# 9xVoice_MikeB_TH_v101.net
KiCad netlist of a schematic drawn in EAGLE
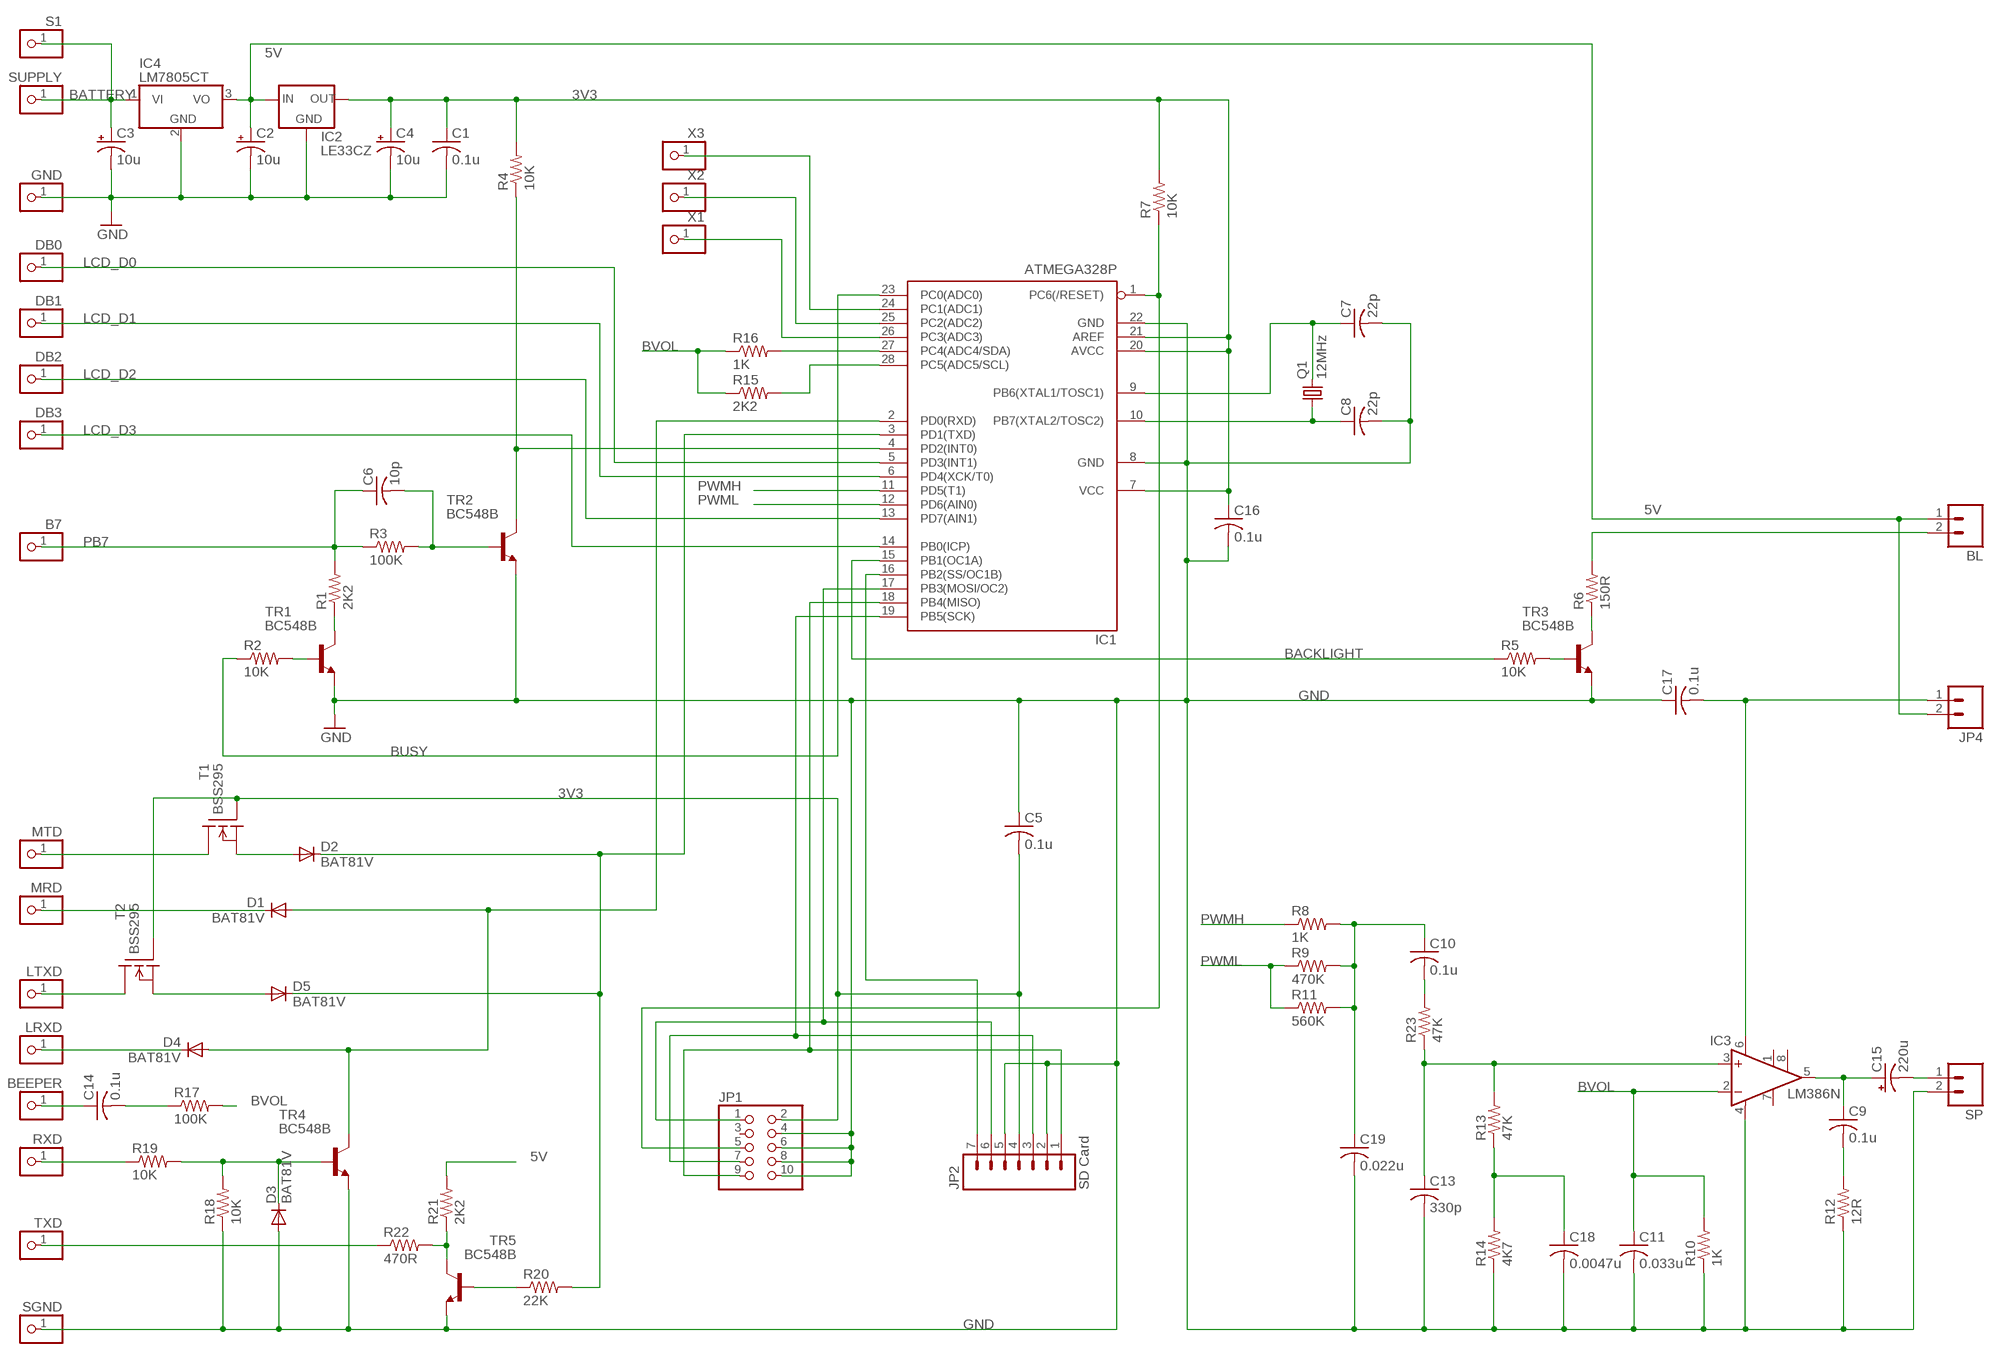
[diagram p0: schematic, sheet 1]

(export (version "E")
  (design (tool "Eeschema 10.0.6"))
  (components
    (comp (ref "B7")
      (value "PINHD-1X1")
      (footprint "eagle-import:1X01")
      (libsource (lib "eagle-import") (part "PINHD-1X1"))
    )
    (comp (ref "BEEPER")
      (value "PINHD-1X1")
      (footprint "eagle-import:1X01")
      (libsource (lib "eagle-import") (part "PINHD-1X1"))
    )
    (comp (ref "BL")
      (value "M02PTH")
      (footprint "eagle-import:1X02")
      (libsource (lib "eagle-import") (part "M02PTH"))
    )
    (comp (ref "C1")
      (value "0.1u")
      (footprint "eagle-import:C025-024X044")
      (libsource (lib "eagle-import") (part "C-US025-024X044"))
    )
    (comp (ref "C2")
      (value "10u")
      (footprint "eagle-import:E1,8-4")
      (libsource (lib "eagle-import") (part "CPOL-USE1.8-4"))
    )
    (comp (ref "C3")
      (value "10u")
      (footprint "eagle-import:E1,8-4")
      (libsource (lib "eagle-import") (part "CPOL-USE1.8-4"))
    )
    (comp (ref "C4")
      (value "10u")
      (footprint "eagle-import:E1,8-4")
      (libsource (lib "eagle-import") (part "CPOL-USE1.8-4"))
    )
    (comp (ref "C5")
      (value "0.1u")
      (footprint "eagle-import:C025-024X044")
      (libsource (lib "eagle-import") (part "C-US025-024X044"))
    )
    (comp (ref "C6")
      (value "10p")
      (footprint "eagle-import:C025-024X044")
      (libsource (lib "eagle-import") (part "C-US025-024X044"))
    )
    (comp (ref "C7")
      (value "22p")
      (footprint "eagle-import:C025-024X044")
      (libsource (lib "eagle-import") (part "C-US025-024X044"))
    )
    (comp (ref "C8")
      (value "22p")
      (footprint "eagle-import:C025-024X044")
      (libsource (lib "eagle-import") (part "C-US025-024X044"))
    )
    (comp (ref "C9")
      (value "0.1u")
      (footprint "eagle-import:C025-024X044")
      (libsource (lib "eagle-import") (part "C-US025-024X044"))
    )
    (comp (ref "C10")
      (value "0.1u")
      (footprint "eagle-import:C025-024X044")
      (libsource (lib "eagle-import") (part "C-US025-024X044"))
    )
    (comp (ref "C11")
      (value "0.033u")
      (footprint "eagle-import:C025-024X044")
      (libsource (lib "eagle-import") (part "C-US025-024X044"))
    )
    (comp (ref "C13")
      (value "330p")
      (footprint "eagle-import:C025-024X044")
      (libsource (lib "eagle-import") (part "C-US025-024X044"))
    )
    (comp (ref "C14")
      (value "0.1u")
      (footprint "eagle-import:C025-024X044")
      (libsource (lib "eagle-import") (part "C-US025-024X044"))
    )
    (comp (ref "C15")
      (value "220u")
      (footprint "eagle-import:E2,5-6")
      (libsource (lib "eagle-import") (part "CPOL-USE2.5-6"))
    )
    (comp (ref "C16")
      (value "0.1u")
      (footprint "eagle-import:C025-024X044")
      (libsource (lib "eagle-import") (part "C-US025-024X044"))
    )
    (comp (ref "C17")
      (value "0.1u")
      (footprint "eagle-import:C025-024X044")
      (libsource (lib "eagle-import") (part "C-US025-024X044"))
    )
    (comp (ref "C18")
      (value "0.0047u")
      (footprint "eagle-import:C025-024X044")
      (libsource (lib "eagle-import") (part "C-US025-024X044"))
    )
    (comp (ref "C19")
      (value "0.022u")
      (footprint "eagle-import:C025-024X044")
      (libsource (lib "eagle-import") (part "C-US025-024X044"))
    )
    (comp (ref "D1")
      (value "BAT81V")
      (footprint "eagle-import:D-2.5")
      (libsource (lib "eagle-import") (part "DIODE-D-2.5"))
    )
    (comp (ref "D2")
      (value "BAT81V")
      (footprint "eagle-import:D-2.5")
      (libsource (lib "eagle-import") (part "DIODE-D-2.5"))
    )
    (comp (ref "D3")
      (value "BAT81V")
      (footprint "eagle-import:D-2.5")
      (libsource (lib "eagle-import") (part "DIODE-D-2.5"))
    )
    (comp (ref "D4")
      (value "BAT81V")
      (footprint "eagle-import:D-2.5")
      (libsource (lib "eagle-import") (part "DIODE-D-2.5"))
    )
    (comp (ref "D5")
      (value "BAT81V")
      (footprint "eagle-import:D-2.5")
      (libsource (lib "eagle-import") (part "DIODE-D-2.5"))
    )
    (comp (ref "DB0")
      (value "PINHD-1X1")
      (footprint "eagle-import:1X01")
      (libsource (lib "eagle-import") (part "PINHD-1X1"))
    )
    (comp (ref "DB1")
      (value "PINHD-1X1")
      (footprint "eagle-import:1X01")
      (libsource (lib "eagle-import") (part "PINHD-1X1"))
    )
    (comp (ref "DB2")
      (value "PINHD-1X1")
      (footprint "eagle-import:1X01")
      (libsource (lib "eagle-import") (part "PINHD-1X1"))
    )
    (comp (ref "DB3")
      (value "PINHD-1X1")
      (footprint "eagle-import:1X01")
      (libsource (lib "eagle-import") (part "PINHD-1X1"))
    )
    (comp (ref "GND")
      (value "PINHD-1X1")
      (footprint "eagle-import:1X01")
      (libsource (lib "eagle-import") (part "PINHD-1X1"))
    )
    (comp (ref "IC1")
      (value "ATMEGA328P")
      (footprint "eagle-import:DIL28-3")
      (libsource (lib "eagle-import") (part "MEGA8-P"))
    )
    (comp (ref "IC2")
      (value "LE33CZ")
      (footprint "eagle-import:78LXX")
      (libsource (lib "eagle-import") (part "78LXX"))
    )
    (comp (ref "IC3")
      (value "LM386N")
      (footprint "eagle-import:DIL08")
      (libsource (lib "eagle-import") (part "LM386?-N1"))
    )
    (comp (ref "IC4")
      (value "LM7805CT")
      (footprint "eagle-import:TO220H")
      (libsource (lib "eagle-import") (part "78T05"))
    )
    (comp (ref "JP1")
      (value "PINHD-2X5")
      (footprint "eagle-import:2X05")
      (libsource (lib "eagle-import") (part "PINHD-2X5"))
    )
    (comp (ref "JP2")
      (value "SD Card")
      (footprint "eagle-import:1X07")
      (libsource (lib "eagle-import") (part "M07"))
    )
    (comp (ref "JP4")
      (value "M02PTH")
      (footprint "eagle-import:1X02")
      (libsource (lib "eagle-import") (part "M02PTH"))
    )
    (comp (ref "LRXD")
      (value "PINHD-1X1")
      (footprint "eagle-import:1X01")
      (libsource (lib "eagle-import") (part "PINHD-1X1"))
    )
    (comp (ref "LTXD")
      (value "PINHD-1X1")
      (footprint "eagle-import:1X01")
      (libsource (lib "eagle-import") (part "PINHD-1X1"))
    )
    (comp (ref "MRD")
      (value "PINHD-1X1")
      (footprint "eagle-import:1X01")
      (libsource (lib "eagle-import") (part "PINHD-1X1"))
    )
    (comp (ref "MTD")
      (value "PINHD-1X1")
      (footprint "eagle-import:1X01")
      (libsource (lib "eagle-import") (part "PINHD-1X1"))
    )
    (comp (ref "Q1")
      (value "12MHz")
      (footprint "eagle-import:HC49US")
      (libsource (lib "eagle-import") (part "CRYSTALHC49US"))
    )
    (comp (ref "R1")
      (value "2K2")
      (footprint "eagle-import:0207_2V")
      (libsource (lib "eagle-import") (part "R-US_0207/2V"))
    )
    (comp (ref "R2")
      (value "10K")
      (footprint "eagle-import:0207_10")
      (libsource (lib "eagle-import") (part "R-US_0207/10"))
    )
    (comp (ref "R3")
      (value "100K")
      (footprint "eagle-import:0207_2V")
      (libsource (lib "eagle-import") (part "R-US_0207/2V"))
    )
    (comp (ref "R4")
      (value "10K")
      (footprint "eagle-import:0207_2V")
      (libsource (lib "eagle-import") (part "R-US_0207/2V"))
    )
    (comp (ref "R5")
      (value "10K")
      (footprint "eagle-import:0207_2V")
      (libsource (lib "eagle-import") (part "R-US_0207/2V"))
    )
    (comp (ref "R6")
      (value "150R")
      (footprint "eagle-import:0207_2V")
      (libsource (lib "eagle-import") (part "R-US_0207/2V"))
    )
    (comp (ref "R7")
      (value "10K")
      (footprint "eagle-import:0207_2V")
      (libsource (lib "eagle-import") (part "R-US_0207/2V"))
    )
    (comp (ref "R8")
      (value "1K")
      (footprint "eagle-import:0207_2V")
      (libsource (lib "eagle-import") (part "R-US_0207/2V"))
    )
    (comp (ref "R9")
      (value "470K")
      (footprint "eagle-import:0207_2V")
      (libsource (lib "eagle-import") (part "R-US_0207/2V"))
    )
    (comp (ref "R10")
      (value "1K")
      (footprint "eagle-import:0207_2V")
      (libsource (lib "eagle-import") (part "R-US_0207/2V"))
    )
    (comp (ref "R11")
      (value "560K")
      (footprint "eagle-import:0207_2V")
      (libsource (lib "eagle-import") (part "R-US_0207/2V"))
    )
    (comp (ref "R12")
      (value "12R")
      (footprint "eagle-import:0207_2V")
      (libsource (lib "eagle-import") (part "R-US_0207/2V"))
    )
    (comp (ref "R13")
      (value "47K")
      (footprint "eagle-import:0207_2V")
      (libsource (lib "eagle-import") (part "R-US_0207/2V"))
    )
    (comp (ref "R14")
      (value "4K7")
      (footprint "eagle-import:0207_2V")
      (libsource (lib "eagle-import") (part "R-US_0207/2V"))
    )
    (comp (ref "R15")
      (value "2K2")
      (footprint "eagle-import:0207_2V")
      (libsource (lib "eagle-import") (part "R-US_0207/2V"))
    )
    (comp (ref "R16")
      (value "1K")
      (footprint "eagle-import:0207_2V")
      (libsource (lib "eagle-import") (part "R-US_0207/2V"))
    )
    (comp (ref "R17")
      (value "100K")
      (footprint "eagle-import:0207_2V")
      (libsource (lib "eagle-import") (part "R-US_0207/2V"))
    )
    (comp (ref "R18")
      (value "10K")
      (footprint "eagle-import:0207_2V")
      (libsource (lib "eagle-import") (part "R-US_0207/2V"))
    )
    (comp (ref "R19")
      (value "10K")
      (footprint "eagle-import:0207_2V")
      (libsource (lib "eagle-import") (part "R-US_0207/2V"))
    )
    (comp (ref "R20")
      (value "22K")
      (footprint "eagle-import:0207_2V")
      (libsource (lib "eagle-import") (part "R-US_0207/2V"))
    )
    (comp (ref "R21")
      (value "2K2")
      (footprint "eagle-import:0207_2V")
      (libsource (lib "eagle-import") (part "R-US_0207/2V"))
    )
    (comp (ref "R22")
      (value "470R")
      (footprint "eagle-import:0207_2V")
      (libsource (lib "eagle-import") (part "R-US_0207/2V"))
    )
    (comp (ref "R23")
      (value "47K")
      (footprint "eagle-import:0207_2V")
      (libsource (lib "eagle-import") (part "R-US_0207/2V"))
    )
    (comp (ref "RXD")
      (value "PINHD-1X1")
      (footprint "eagle-import:1X01")
      (libsource (lib "eagle-import") (part "PINHD-1X1"))
    )
    (comp (ref "S1")
      (value "PINHD-1X1")
      (footprint "eagle-import:1X01")
      (libsource (lib "eagle-import") (part "PINHD-1X1"))
    )
    (comp (ref "SGND")
      (value "PINHD-1X1")
      (footprint "eagle-import:1X01")
      (libsource (lib "eagle-import") (part "PINHD-1X1"))
    )
    (comp (ref "SP")
      (value "M02PTH")
      (footprint "eagle-import:1X02")
      (libsource (lib "eagle-import") (part "M02PTH"))
    )
    (comp (ref "SUPPLY")
      (value "PINHD-1X1")
      (footprint "eagle-import:1X01")
      (libsource (lib "eagle-import") (part "PINHD-1X1"))
    )
    (comp (ref "T1")
      (value "BSS295")
      (footprint "eagle-import:TO92")
      (libsource (lib "eagle-import") (part "BSS295"))
    )
    (comp (ref "T2")
      (value "BSS295")
      (footprint "eagle-import:TO92")
      (libsource (lib "eagle-import") (part "BSS295"))
    )
    (comp (ref "TR1")
      (value "BC548B")
      (footprint "eagle-import:TO92-EBC")
      (libsource (lib "eagle-import") (part "BC548B"))
    )
    (comp (ref "TR2")
      (value "BC548B")
      (footprint "eagle-import:TO92-EBC")
      (libsource (lib "eagle-import") (part "BC548B"))
    )
    (comp (ref "TR3")
      (value "BC548B")
      (footprint "eagle-import:TO92-EBC")
      (libsource (lib "eagle-import") (part "BC548B"))
    )
    (comp (ref "TR4")
      (value "BC548B")
      (footprint "eagle-import:TO92-EBC")
      (libsource (lib "eagle-import") (part "BC548B"))
    )
    (comp (ref "TR5")
      (value "BC548B")
      (footprint "eagle-import:TO92-EBC")
      (libsource (lib "eagle-import") (part "BC548B"))
    )
    (comp (ref "TXD")
      (value "PINHD-1X1")
      (footprint "eagle-import:1X01")
      (libsource (lib "eagle-import") (part "PINHD-1X1"))
    )
    (comp (ref "X1")
      (value "PINHD-1X1")
      (footprint "eagle-import:1X01")
      (libsource (lib "eagle-import") (part "PINHD-1X1"))
    )
    (comp (ref "X2")
      (value "PINHD-1X1")
      (footprint "eagle-import:1X01")
      (libsource (lib "eagle-import") (part "PINHD-1X1"))
    )
    (comp (ref "X3")
      (value "PINHD-1X1")
      (footprint "eagle-import:1X01")
      (libsource (lib "eagle-import") (part "PINHD-1X1"))
    )
  )
  (nets
    (net (code "1") (name "/3V3") (class "Default")
      (node (ref "C1") (pin "1") (pinfunction "1_1") (pintype "passive"))
      (node (ref "C16") (pin "1") (pinfunction "1_1") (pintype "passive"))
      (node (ref "C4") (pin "+") (pinfunction "+_+") (pintype "passive"))
      (node (ref "C5") (pin "2") (pinfunction "2_2") (pintype "passive"))
      (node (ref "IC1") (pin "20") (pinfunction "AVCC_20") (pintype "power_in"))
      (node (ref "IC1") (pin "21") (pinfunction "AREF_21") (pintype "passive"))
      (node (ref "IC1") (pin "7") (pinfunction "VCC_7") (pintype "power_in"))
      (node (ref "IC2") (pin "OUT") (pinfunction "OUT_OUT") (pintype "passive"))
      (node (ref "JP1") (pin "2") (pinfunction "2_2") (pintype "passive"))
      (node (ref "JP2") (pin "4") (pinfunction "4_4") (pintype "passive"))
      (node (ref "R4") (pin "2") (pinfunction "2_2") (pintype "passive"))
      (node (ref "R7") (pin "2") (pinfunction "2_2") (pintype "passive"))
      (node (ref "T1") (pin "1") (pinfunction "G_1") (pintype "passive"))
      (node (ref "T2") (pin "1") (pinfunction "G_1") (pintype "passive"))
    )
    (net (code "2") (name "/5V") (class "Default")
      (node (ref "BL") (pin "1") (pinfunction "1_1") (pintype "passive"))
      (node (ref "C2") (pin "+") (pinfunction "+_+") (pintype "passive"))
      (node (ref "IC2") (pin "IN") (pinfunction "IN_IN") (pintype "input"))
      (node (ref "IC4") (pin "3") (pinfunction "VO_3") (pintype "passive"))
      (node (ref "JP4") (pin "2") (pinfunction "2_2") (pintype "passive"))
      (node (ref "R21") (pin "2") (pinfunction "2_2") (pintype "passive"))
    )
    (net (code "3") (name "/BACKLIGHT") (class "Default")
      (node (ref "IC1") (pin "15") (pinfunction "PB1(OC1A)_15") (pintype "bidirectional"))
      (node (ref "R5") (pin "1") (pinfunction "1_1") (pintype "passive"))
    )
    (net (code "4") (name "/BATTERY") (class "Default")
      (node (ref "C3") (pin "+") (pinfunction "+_+") (pintype "passive"))
      (node (ref "IC4") (pin "1") (pinfunction "VI_1") (pintype "input"))
      (node (ref "S1") (pin "1") (pinfunction "1_1") (pintype "passive"))
      (node (ref "SUPPLY") (pin "1") (pinfunction "1_1") (pintype "passive"))
    )
    (net (code "5") (name "/BUSY") (class "Default")
      (node (ref "IC1") (pin "23") (pinfunction "PC0(ADC0)_23") (pintype "bidirectional"))
      (node (ref "R2") (pin "1") (pinfunction "1_1") (pintype "passive"))
    )
    (net (code "6") (name "/BVOL") (class "Default")
      (node (ref "C11") (pin "1") (pinfunction "1_1") (pintype "passive"))
      (node (ref "IC3") (pin "2") (pinfunction "-IN_2") (pintype "input"))
      (node (ref "R10") (pin "2") (pinfunction "2_2") (pintype "passive"))
      (node (ref "R15") (pin "1") (pinfunction "1_1") (pintype "passive"))
      (node (ref "R16") (pin "1") (pinfunction "1_1") (pintype "passive"))
      (node (ref "R17") (pin "2") (pinfunction "2_2") (pintype "passive"))
    )
    (net (code "7") (name "/LCD_D0") (class "Default")
      (node (ref "DB0") (pin "1") (pinfunction "1_1") (pintype "passive"))
      (node (ref "IC1") (pin "5") (pinfunction "PD3(INT1)_5") (pintype "bidirectional"))
    )
    (net (code "8") (name "/LCD_D1") (class "Default")
      (node (ref "DB1") (pin "1") (pinfunction "1_1") (pintype "passive"))
      (node (ref "IC1") (pin "6") (pinfunction "PD4(XCK/T0)_6") (pintype "bidirectional"))
    )
    (net (code "9") (name "/LCD_D2") (class "Default")
      (node (ref "DB2") (pin "1") (pinfunction "1_1") (pintype "passive"))
      (node (ref "IC1") (pin "13") (pinfunction "PD7(AIN1)_13") (pintype "bidirectional"))
    )
    (net (code "10") (name "/LCD_D3") (class "Default")
      (node (ref "DB3") (pin "1") (pinfunction "1_1") (pintype "passive"))
      (node (ref "IC1") (pin "14") (pinfunction "PB0(ICP)_14") (pintype "bidirectional"))
    )
    (net (code "11") (name "/PB7") (class "Default")
      (node (ref "B7") (pin "1") (pinfunction "1_1") (pintype "passive"))
      (node (ref "C6") (pin "1") (pinfunction "1_1") (pintype "passive"))
      (node (ref "R1") (pin "2") (pinfunction "2_2") (pintype "passive"))
      (node (ref "R3") (pin "1") (pinfunction "1_1") (pintype "passive"))
    )
    (net (code "12") (name "/PWMH") (class "Default")
      (node (ref "IC1") (pin "11") (pinfunction "PD5(T1)_11") (pintype "bidirectional"))
      (node (ref "R8") (pin "1") (pinfunction "1_1") (pintype "passive"))
    )
    (net (code "13") (name "/PWML") (class "Default")
      (node (ref "IC1") (pin "12") (pinfunction "PD6(AIN0)_12") (pintype "bidirectional"))
      (node (ref "R11") (pin "1") (pinfunction "1_1") (pintype "passive"))
      (node (ref "R9") (pin "1") (pinfunction "1_1") (pintype "passive"))
    )
    (net (code "14") (name "GND") (class "Default")
      (node (ref "C1") (pin "2") (pinfunction "2_2") (pintype "passive"))
      (node (ref "C11") (pin "2") (pinfunction "2_2") (pintype "passive"))
      (node (ref "C13") (pin "2") (pinfunction "2_2") (pintype "passive"))
      (node (ref "C16") (pin "2") (pinfunction "2_2") (pintype "passive"))
      (node (ref "C17") (pin "1") (pinfunction "1_1") (pintype "passive"))
      (node (ref "C18") (pin "2") (pinfunction "2_2") (pintype "passive"))
      (node (ref "C19") (pin "2") (pinfunction "2_2") (pintype "passive"))
      (node (ref "C2") (pin "-") (pinfunction "-_-") (pintype "passive"))
      (node (ref "C3") (pin "-") (pinfunction "-_-") (pintype "passive"))
      (node (ref "C4") (pin "-") (pinfunction "-_-") (pintype "passive"))
      (node (ref "C5") (pin "1") (pinfunction "1_1") (pintype "passive"))
      (node (ref "C7") (pin "2") (pinfunction "2_2") (pintype "passive"))
      (node (ref "C8") (pin "2") (pinfunction "2_2") (pintype "passive"))
      (node (ref "D3") (pin "A") (pinfunction "A_A") (pintype "passive"))
      (node (ref "GND") (pin "1") (pinfunction "1_1") (pintype "passive"))
      (node (ref "IC1") (pin "22") (pinfunction "GND_22") (pintype "power_in"))
      (node (ref "IC1") (pin "8") (pinfunction "GND_8") (pintype "power_in"))
      (node (ref "IC2") (pin "GND") (pinfunction "GND_GND") (pintype "input"))
      (node (ref "IC3") (pin "4") (pinfunction "GND_4") (pintype "power_in"))
      (node (ref "IC4") (pin "2") (pinfunction "GND_2") (pintype "passive"))
      (node (ref "JP1") (pin "10") (pinfunction "10_10") (pintype "passive"))
      (node (ref "JP1") (pin "4") (pinfunction "4_4") (pintype "passive"))
      (node (ref "JP1") (pin "6") (pinfunction "6_6") (pintype "passive"))
      (node (ref "JP1") (pin "8") (pinfunction "8_8") (pintype "passive"))
      (node (ref "JP2") (pin "2") (pinfunction "2_2") (pintype "passive"))
      (node (ref "JP2") (pin "5") (pinfunction "5_5") (pintype "passive"))
      (node (ref "R10") (pin "1") (pinfunction "1_1") (pintype "passive"))
      (node (ref "R12") (pin "1") (pinfunction "1_1") (pintype "passive"))
      (node (ref "R14") (pin "1") (pinfunction "1_1") (pintype "passive"))
      (node (ref "R18") (pin "1") (pinfunction "1_1") (pintype "passive"))
      (node (ref "SGND") (pin "1") (pinfunction "1_1") (pintype "passive"))
      (node (ref "SP") (pin "2") (pinfunction "2_2") (pintype "passive"))
      (node (ref "TR1") (pin "E") (pinfunction "E_E") (pintype "passive"))
      (node (ref "TR2") (pin "E") (pinfunction "E_E") (pintype "passive"))
      (node (ref "TR3") (pin "E") (pinfunction "E_E") (pintype "passive"))
      (node (ref "TR4") (pin "E") (pinfunction "E_E") (pintype "passive"))
      (node (ref "TR5") (pin "E") (pinfunction "E_E") (pintype "passive"))
    )
    (net (code "15") (name "Net-(BEEPER-Pad1)") (class "Default")
      (node (ref "BEEPER") (pin "1") (pinfunction "1_1") (pintype "passive"))
      (node (ref "C14") (pin "1") (pinfunction "1_1") (pintype "passive"))
    )
    (net (code "16") (name "Net-(BL-Pad2)") (class "Default")
      (node (ref "BL") (pin "2") (pinfunction "2_2") (pintype "passive"))
      (node (ref "R6") (pin "2") (pinfunction "2_2") (pintype "passive"))
    )
    (net (code "17") (name "Net-(C6-Pad2)") (class "Default")
      (node (ref "C6") (pin "2") (pinfunction "2_2") (pintype "passive"))
      (node (ref "R3") (pin "2") (pinfunction "2_2") (pintype "passive"))
      (node (ref "TR2") (pin "B") (pinfunction "B_B") (pintype "passive"))
    )
    (net (code "18") (name "Net-(C9-Pad2)") (class "Default")
      (node (ref "C9") (pin "2") (pinfunction "2_2") (pintype "passive"))
      (node (ref "R12") (pin "2") (pinfunction "2_2") (pintype "passive"))
    )
    (net (code "19") (name "Net-(C10-Pad1)") (class "Default")
      (node (ref "C10") (pin "1") (pinfunction "1_1") (pintype "passive"))
      (node (ref "C19") (pin "1") (pinfunction "1_1") (pintype "passive"))
      (node (ref "R11") (pin "2") (pinfunction "2_2") (pintype "passive"))
      (node (ref "R8") (pin "2") (pinfunction "2_2") (pintype "passive"))
      (node (ref "R9") (pin "2") (pinfunction "2_2") (pintype "passive"))
    )
    (net (code "20") (name "Net-(C10-Pad2)") (class "Default")
      (node (ref "C10") (pin "2") (pinfunction "2_2") (pintype "passive"))
      (node (ref "R23") (pin "2") (pinfunction "2_2") (pintype "passive"))
    )
    (net (code "21") (name "Net-(C14-Pad2)") (class "Default")
      (node (ref "C14") (pin "2") (pinfunction "2_2") (pintype "passive"))
      (node (ref "R17") (pin "1") (pinfunction "1_1") (pintype "passive"))
    )
    (net (code "22") (name "Net-(C15-Pad-)") (class "Default")
      (node (ref "C15") (pin "-") (pinfunction "-_-") (pintype "passive"))
      (node (ref "SP") (pin "1") (pinfunction "1_1") (pintype "passive"))
    )
    (net (code "23") (name "Net-(C18-Pad1)") (class "Default")
      (node (ref "C18") (pin "1") (pinfunction "1_1") (pintype "passive"))
      (node (ref "R13") (pin "1") (pinfunction "1_1") (pintype "passive"))
      (node (ref "R14") (pin "2") (pinfunction "2_2") (pintype "passive"))
    )
    (net (code "24") (name "Net-(D1-PadC)") (class "Default")
      (node (ref "D1") (pin "C") (pinfunction "C_C") (pintype "passive"))
      (node (ref "MRD") (pin "1") (pinfunction "1_1") (pintype "passive"))
    )
    (net (code "25") (name "Net-(D3-PadC)") (class "Default")
      (node (ref "D3") (pin "C") (pinfunction "C_C") (pintype "passive"))
      (node (ref "R18") (pin "2") (pinfunction "2_2") (pintype "passive"))
      (node (ref "R19") (pin "2") (pinfunction "2_2") (pintype "passive"))
      (node (ref "TR4") (pin "B") (pinfunction "B_B") (pintype "passive"))
    )
    (net (code "26") (name "Net-(D4-PadC)") (class "Default")
      (node (ref "D4") (pin "C") (pinfunction "C_C") (pintype "passive"))
      (node (ref "LRXD") (pin "1") (pinfunction "1_1") (pintype "passive"))
    )
    (net (code "27") (name "Net-(IC1-PB2(SS{slash}OC1B))") (class "Default")
      (node (ref "IC1") (pin "16") (pinfunction "PB2(SS/OC1B)_16") (pintype "bidirectional"))
      (node (ref "JP2") (pin "7") (pinfunction "7_7") (pintype "passive"))
    )
    (net (code "28") (name "Net-(IC1-PB3(MOSI{slash}OC2))") (class "Default")
      (node (ref "IC1") (pin "17") (pinfunction "PB3(MOSI/OC2)_17") (pintype "bidirectional"))
      (node (ref "JP1") (pin "1") (pinfunction "1_1") (pintype "passive"))
      (node (ref "JP2") (pin "6") (pinfunction "6_6") (pintype "passive"))
    )
    (net (code "29") (name "Net-(IC1-PB4(MISO))") (class "Default")
      (node (ref "IC1") (pin "18") (pinfunction "PB4(MISO)_18") (pintype "bidirectional"))
      (node (ref "JP1") (pin "9") (pinfunction "9_9") (pintype "passive"))
      (node (ref "JP2") (pin "1") (pinfunction "1_1") (pintype "passive"))
    )
    (net (code "30") (name "Net-(IC1-PB5(SCK))") (class "Default")
      (node (ref "IC1") (pin "19") (pinfunction "PB5(SCK)_19") (pintype "bidirectional"))
      (node (ref "JP1") (pin "7") (pinfunction "7_7") (pintype "passive"))
      (node (ref "JP2") (pin "3") (pinfunction "3_3") (pintype "passive"))
    )
    (net (code "31") (name "Net-(IC1-PB6(XTAL1{slash}TOSC1))") (class "Default")
      (node (ref "C7") (pin "1") (pinfunction "1_1") (pintype "passive"))
      (node (ref "IC1") (pin "9") (pinfunction "PB6(XTAL1/TOSC1)_9") (pintype "bidirectional"))
      (node (ref "Q1") (pin "2") (pinfunction "2_2") (pintype "passive"))
    )
    (net (code "32") (name "Net-(IC1-PB7(XTAL2{slash}TOSC2))") (class "Default")
      (node (ref "C8") (pin "1") (pinfunction "1_1") (pintype "passive"))
      (node (ref "IC1") (pin "10") (pinfunction "PB7(XTAL2/TOSC2)_10") (pintype "bidirectional"))
      (node (ref "Q1") (pin "1") (pinfunction "1_1") (pintype "passive"))
    )
    (net (code "33") (name "Net-(IC1-PC1(ADC1))") (class "Default")
      (node (ref "IC1") (pin "24") (pinfunction "PC1(ADC1)_24") (pintype "bidirectional"))
      (node (ref "X3") (pin "1") (pinfunction "1_1") (pintype "passive"))
    )
    (net (code "34") (name "Net-(IC1-PC2(ADC2))") (class "Default")
      (node (ref "IC1") (pin "25") (pinfunction "PC2(ADC2)_25") (pintype "bidirectional"))
      (node (ref "X2") (pin "1") (pinfunction "1_1") (pintype "passive"))
    )
    (net (code "35") (name "Net-(IC1-PC3(ADC3))") (class "Default")
      (node (ref "IC1") (pin "26") (pinfunction "PC3(ADC3)_26") (pintype "bidirectional"))
      (node (ref "X1") (pin "1") (pinfunction "1_1") (pintype "passive"))
    )
    (net (code "36") (name "Net-(IC1-PC4(ADC4{slash}SDA))") (class "Default")
      (node (ref "IC1") (pin "27") (pinfunction "PC4(ADC4/SDA)_27") (pintype "bidirectional"))
      (node (ref "R16") (pin "2") (pinfunction "2_2") (pintype "passive"))
    )
    (net (code "37") (name "Net-(IC1-PC5(ADC5{slash}SCL))") (class "Default")
      (node (ref "IC1") (pin "28") (pinfunction "PC5(ADC5/SCL)_28") (pintype "bidirectional"))
      (node (ref "R15") (pin "2") (pinfunction "2_2") (pintype "passive"))
    )
    (net (code "38") (name "Net-(IC1-PC6({slash}RESET))") (class "Default")
      (node (ref "IC1") (pin "1") (pinfunction "PC6(/RESET)_1") (pintype "bidirectional"))
      (node (ref "JP1") (pin "5") (pinfunction "5_5") (pintype "passive"))
      (node (ref "R7") (pin "1") (pinfunction "1_1") (pintype "passive"))
    )
    (net (code "39") (name "Net-(IC1-PD0(RXD))") (class "Default")
      (node (ref "D1") (pin "A") (pinfunction "A_A") (pintype "passive"))
      (node (ref "D4") (pin "A") (pinfunction "A_A") (pintype "passive"))
      (node (ref "IC1") (pin "2") (pinfunction "PD0(RXD)_2") (pintype "bidirectional"))
      (node (ref "TR4") (pin "C") (pinfunction "C_C") (pintype "passive"))
    )
    (net (code "40") (name "Net-(IC1-PD1(TXD))") (class "Default")
      (node (ref "D2") (pin "C") (pinfunction "C_C") (pintype "passive"))
      (node (ref "D5") (pin "C") (pinfunction "C_C") (pintype "passive"))
      (node (ref "IC1") (pin "3") (pinfunction "PD1(TXD)_3") (pintype "bidirectional"))
      (node (ref "R20") (pin "2") (pinfunction "2_2") (pintype "passive"))
    )
    (net (code "41") (name "Net-(IC1-PD2(INT0))") (class "Default")
      (node (ref "IC1") (pin "4") (pinfunction "PD2(INT0)_4") (pintype "bidirectional"))
      (node (ref "R4") (pin "1") (pinfunction "1_1") (pintype "passive"))
      (node (ref "TR2") (pin "C") (pinfunction "C_C") (pintype "passive"))
    )
    (net (code "42") (name "Net-(IC3-+IN)") (class "Default")
      (node (ref "C13") (pin "1") (pinfunction "1_1") (pintype "passive"))
      (node (ref "IC3") (pin "3") (pinfunction "+IN_3") (pintype "input"))
      (node (ref "R13") (pin "2") (pinfunction "2_2") (pintype "passive"))
      (node (ref "R23") (pin "1") (pinfunction "1_1") (pintype "passive"))
    )
    (net (code "43") (name "Net-(IC3-OUT)") (class "Default")
      (node (ref "C15") (pin "+") (pinfunction "+_+") (pintype "passive"))
      (node (ref "C9") (pin "1") (pinfunction "1_1") (pintype "passive"))
      (node (ref "IC3") (pin "5") (pinfunction "OUT_5") (pintype "output"))
    )
    (net (code "44") (name "Net-(IC3-VS)") (class "Default")
      (node (ref "C17") (pin "2") (pinfunction "2_2") (pintype "passive"))
      (node (ref "IC3") (pin "6") (pinfunction "VS_6") (pintype "power_in"))
      (node (ref "JP4") (pin "1") (pinfunction "1_1") (pintype "passive"))
    )
    (net (code "45") (name "Net-(R1-Pad1)") (class "Default")
      (node (ref "R1") (pin "1") (pinfunction "1_1") (pintype "passive"))
      (node (ref "TR1") (pin "C") (pinfunction "C_C") (pintype "passive"))
    )
    (net (code "46") (name "Net-(R2-Pad2)") (class "Default")
      (node (ref "R2") (pin "2") (pinfunction "2_2") (pintype "passive"))
      (node (ref "TR1") (pin "B") (pinfunction "B_B") (pintype "passive"))
    )
    (net (code "47") (name "Net-(R5-Pad2)") (class "Default")
      (node (ref "R5") (pin "2") (pinfunction "2_2") (pintype "passive"))
      (node (ref "TR3") (pin "B") (pinfunction "B_B") (pintype "passive"))
    )
    (net (code "48") (name "Net-(R6-Pad1)") (class "Default")
      (node (ref "R6") (pin "1") (pinfunction "1_1") (pintype "passive"))
      (node (ref "TR3") (pin "C") (pinfunction "C_C") (pintype "passive"))
    )
    (net (code "49") (name "Net-(R19-Pad1)") (class "Default")
      (node (ref "R19") (pin "1") (pinfunction "1_1") (pintype "passive"))
      (node (ref "RXD") (pin "1") (pinfunction "1_1") (pintype "passive"))
    )
    (net (code "50") (name "Net-(R20-Pad1)") (class "Default")
      (node (ref "R20") (pin "1") (pinfunction "1_1") (pintype "passive"))
      (node (ref "TR5") (pin "B") (pinfunction "B_B") (pintype "passive"))
    )
    (net (code "51") (name "Net-(R21-Pad1)") (class "Default")
      (node (ref "R21") (pin "1") (pinfunction "1_1") (pintype "passive"))
      (node (ref "R22") (pin "2") (pinfunction "2_2") (pintype "passive"))
      (node (ref "TR5") (pin "C") (pinfunction "C_C") (pintype "passive"))
    )
    (net (code "52") (name "Net-(R22-Pad1)") (class "Default")
      (node (ref "R22") (pin "1") (pinfunction "1_1") (pintype "passive"))
      (node (ref "TXD") (pin "1") (pinfunction "1_1") (pintype "passive"))
    )
    (net (code "53") (name "Net-(T1-D)") (class "Default")
      (node (ref "MTD") (pin "1") (pinfunction "1_1") (pintype "passive"))
      (node (ref "T1") (pin "2") (pinfunction "D_2") (pintype "passive"))
    )
    (net (code "54") (name "Net-(T1-S)") (class "Default")
      (node (ref "D2") (pin "A") (pinfunction "A_A") (pintype "passive"))
      (node (ref "T1") (pin "3") (pinfunction "S_3") (pintype "passive"))
    )
    (net (code "55") (name "Net-(T2-D)") (class "Default")
      (node (ref "LTXD") (pin "1") (pinfunction "1_1") (pintype "passive"))
      (node (ref "T2") (pin "2") (pinfunction "D_2") (pintype "passive"))
    )
    (net (code "56") (name "Net-(T2-S)") (class "Default")
      (node (ref "D5") (pin "A") (pinfunction "A_A") (pintype "passive"))
      (node (ref "T2") (pin "3") (pinfunction "S_3") (pintype "passive"))
    )
    (net (code "57") (name "unconnected-(IC3-BYPASS-Pad7)") (class "Default")
      (node (ref "IC3") (pin "7") (pinfunction "BYPASS_7") (pintype "passive"))
    )
    (net (code "58") (name "unconnected-(IC3-GAIN-Pad1)") (class "Default")
      (node (ref "IC3") (pin "1") (pinfunction "GAIN_1") (pintype "passive"))
    )
    (net (code "59") (name "unconnected-(IC3-GAIN-Pad8)") (class "Default")
      (node (ref "IC3") (pin "8") (pinfunction "GAIN_8") (pintype "passive"))
    )
    (net (code "60") (name "unconnected-(JP1-Pad3)") (class "Default")
      (node (ref "JP1") (pin "3") (pinfunction "3_3") (pintype "passive"))
    )
  )
)
